# Fri3D_2024_ESP32.net
KiCad netlist of a schematic drawn in Altium Designer
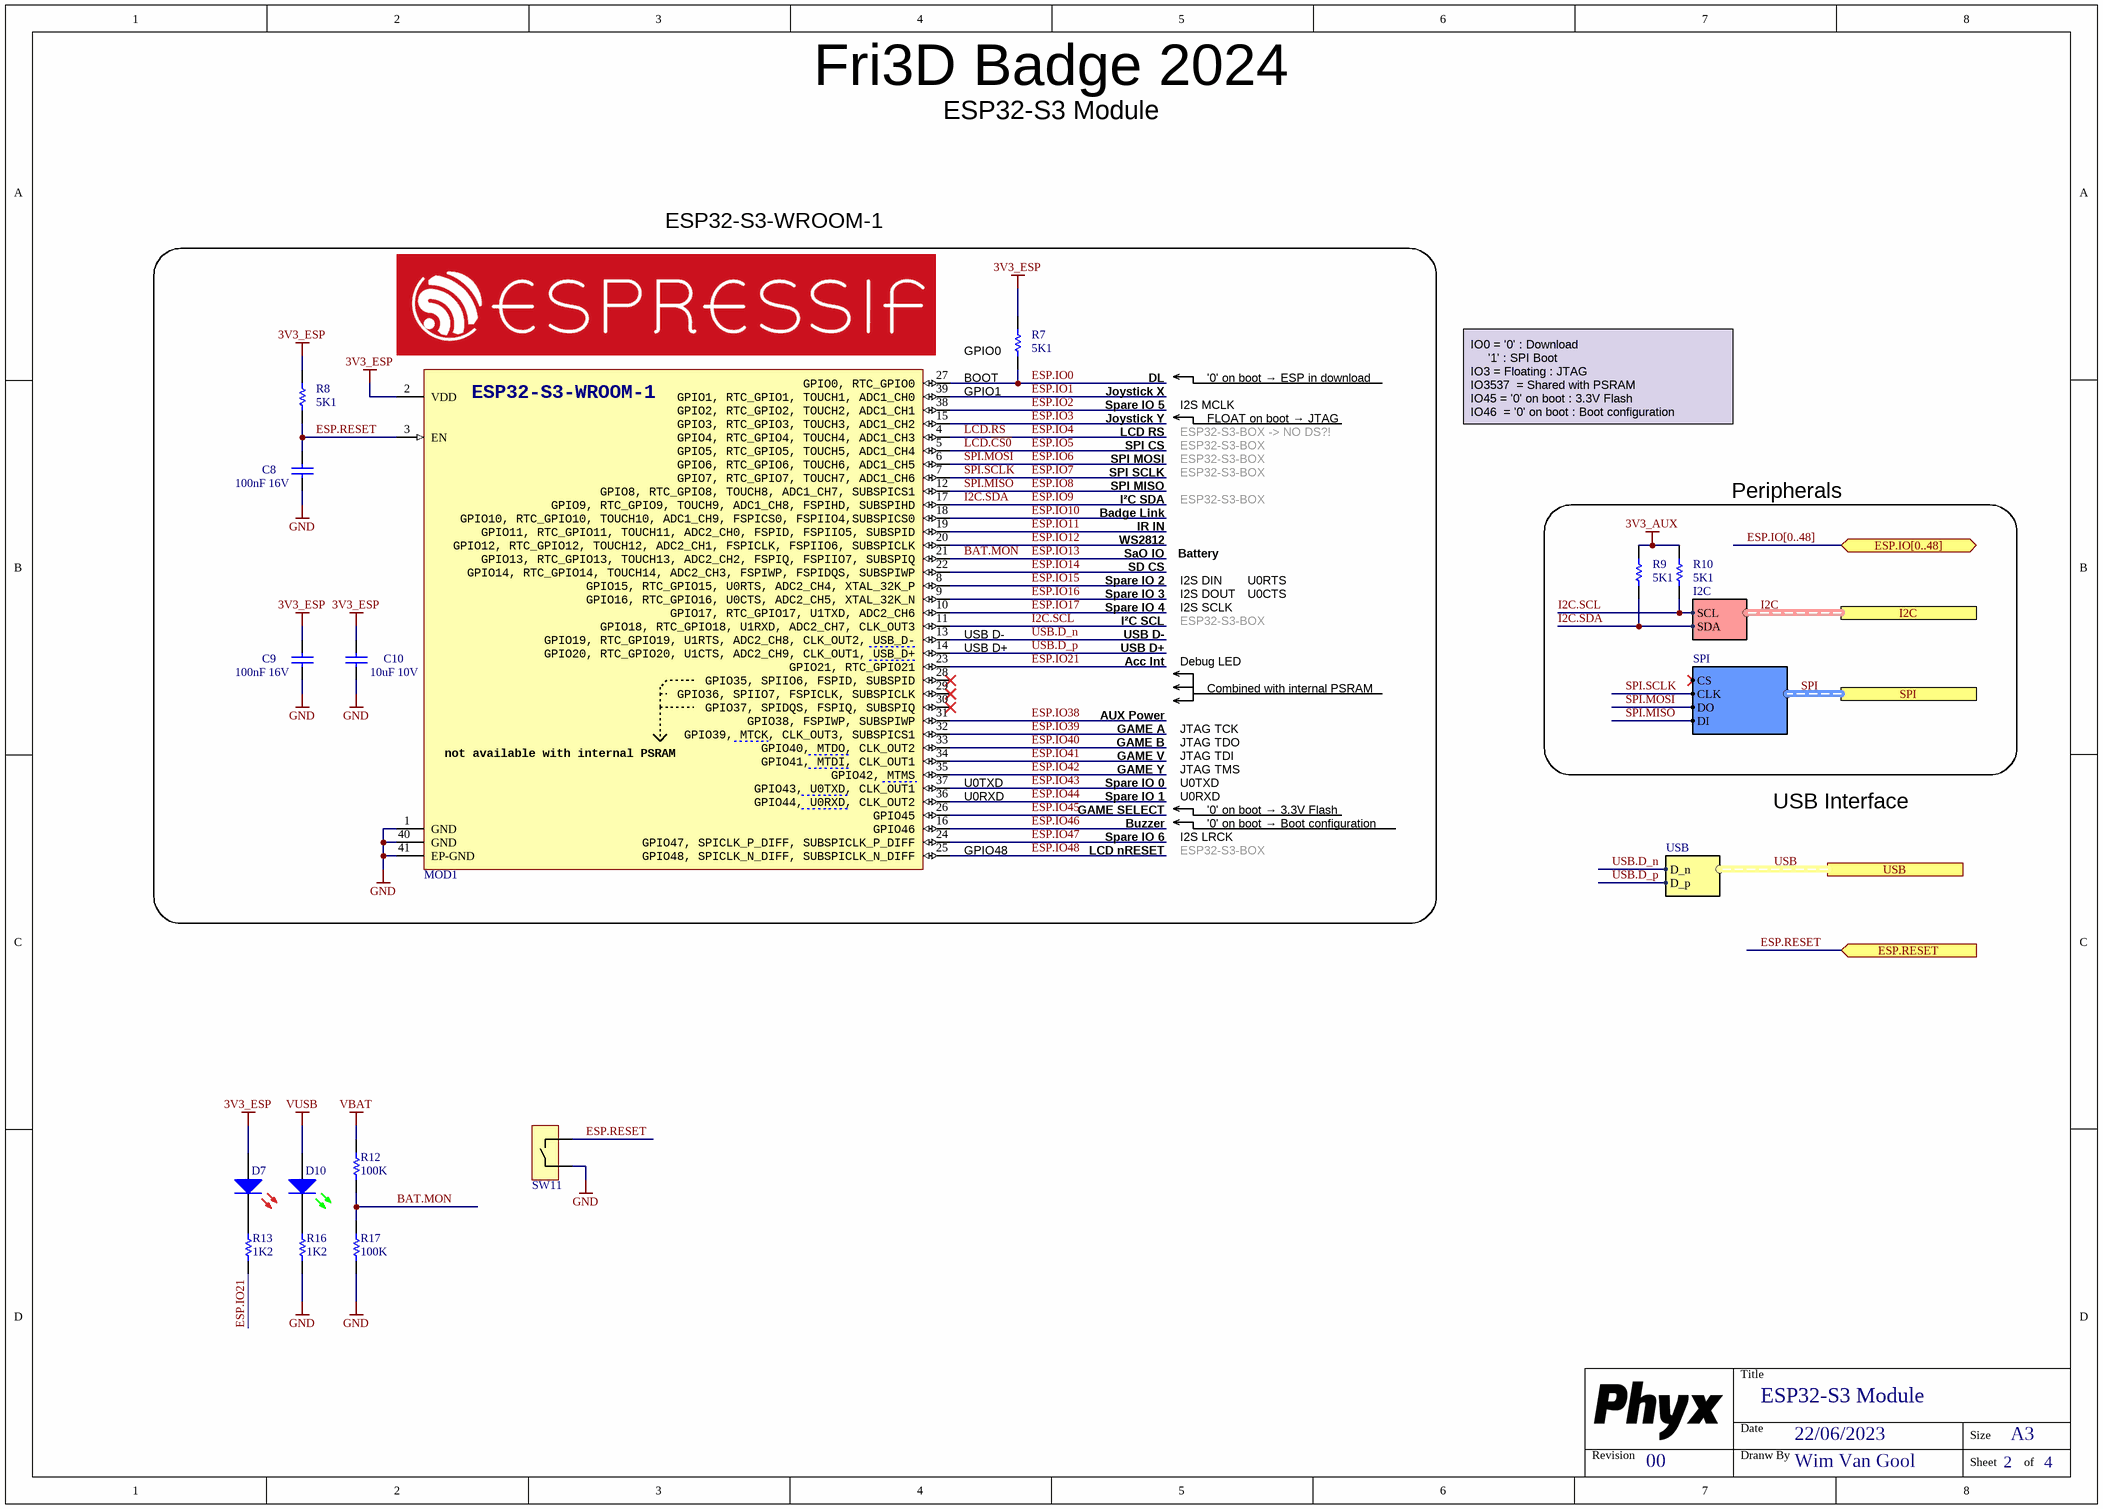
[diagram p0: Fri3D_2024_ESP32.SchDoc]

(export (version "E")
  (design (tool "Eeschema 10.0.6"))
  (components
    (comp (ref "C8")
      (value "100nF 16V")
      (footprint "C0603_N")
      (description "Capacitor Ceramic")
      (libsource (lib "Phyx_Components") (part "CAP_CERAMIC"))
    )
    (comp (ref "C9")
      (value "100nF 16V")
      (footprint "C0603_N")
      (description "Capacitor Ceramic")
      (libsource (lib "Phyx_Components") (part "CAP_CERAMIC"))
    )
    (comp (ref "C10")
      (value "10uF 10V")
      (footprint "C0805_N")
      (description "Capacitor Ceramic")
      (fields (field (name "Comment") "CAP_CERAMIC"))
      (libsource (lib "Phyx_Components") (part "CAP_CERAMIC"))
    )
    (comp (ref "D7")
      (value "Default 0805 Red LED")
      (footprint "LED_0805_RD")
      (description "=Description")
      (libsource (lib "Phyx_Components") (part "LED_RED"))
    )
    (comp (ref "D10")
      (value "Default 0805 Green LED")
      (footprint "LED_0805_GR")
      (description "=Description")
      (libsource (lib "Phyx_Components") (part "LED_GREEN"))
    )
    (comp (ref "MOD1")
      (value "ESP32-S3 based WROOM-1 16MB Flash, 8MB PSRAM")
      (footprint "ESP-ESP32-S3-WROOM-1")
      (description "WiFi # MOD ESP32-S3-WROOM-1")
      (libsource (lib "Phyx_Components") (part "ESP-ESP32-S3-WROOM-1"))
    )
    (comp (ref "R7")
      (value "5K1")
      (footprint "R0603_N")
      (fields (field (name "Comment") "RESISTOR"))
      (libsource (lib "Phyx_Components") (part "RESISTOR"))
    )
    (comp (ref "R8")
      (value "5K1")
      (footprint "R0603_N")
      (fields (field (name "Comment") "RESISTOR"))
      (libsource (lib "Phyx_Components") (part "RESISTOR"))
    )
    (comp (ref "R9")
      (value "5K1")
      (footprint "R0603_N")
      (fields (field (name "Comment") "RESISTOR"))
      (libsource (lib "Phyx_Components") (part "RESISTOR"))
    )
    (comp (ref "R10")
      (value "5K1")
      (footprint "R0603_N")
      (fields (field (name "Comment") "RESISTOR"))
      (libsource (lib "Phyx_Components") (part "RESISTOR"))
    )
    (comp (ref "R12")
      (value "100K")
      (footprint "R0603_N")
      (fields (field (name "Comment") "RESISTOR"))
      (libsource (lib "Phyx_Components") (part "RESISTOR"))
    )
    (comp (ref "R13")
      (value "1K2")
      (footprint "R0603_N")
      (fields (field (name "Comment") "RESISTOR"))
      (libsource (lib "Phyx_Components") (part "RESISTOR"))
    )
    (comp (ref "R16")
      (value "1K2")
      (footprint "R0603_N")
      (fields (field (name "Comment") "RESISTOR"))
      (libsource (lib "Phyx_Components") (part "RESISTOR"))
    )
    (comp (ref "R17")
      (value "100K")
      (footprint "R0603_N")
      (fields (field (name "Comment") "RESISTOR"))
      (libsource (lib "Phyx_Components") (part "RESISTOR"))
    )
    (comp (ref "SW11")
      (value "SKPMAME010 6x6 TACTG Switch")
      (footprint "ALPS_SKPMAME010")
      (libsource (lib "Phyx_Components") (part "SW_TACT"))
    )
  )
  (nets
    (net (code "23") (name "/ESP.IO0") (class "Default")
      (node (ref "MOD1") (pin "27") (pinfunction "GPIO0,_RTC_GPIO0_27") (pintype "bidirectional"))
      (node (ref "R7") (pin "2") (pinfunction "2_2") (pintype "passive"))
    )
    (net (code "24") (name "/ESP.IO1") (class "Default")
      (node (ref "MOD1") (pin "39") (pinfunction "GPIO1,_RTC_GPIO1,_TOUCH1,_ADC1_CH0_39") (pintype "bidirectional"))
    )
    (net (code "25") (name "/ESP.IO2") (class "Default")
      (node (ref "MOD1") (pin "38") (pinfunction "GPIO2,_RTC_GPIO2,_TOUCH2,_ADC1_CH1_38") (pintype "bidirectional"))
    )
    (net (code "26") (name "/ESP.IO3") (class "Default")
      (node (ref "MOD1") (pin "15") (pinfunction "GPIO3,_RTC_GPIO3,_TOUCH3,_ADC1_CH2_15") (pintype "bidirectional"))
    )
    (net (code "27") (name "/ESP.IO4") (class "Default")
      (node (ref "MOD1") (pin "4") (pinfunction "GPIO4,_RTC_GPIO4,_TOUCH4,_ADC1_CH3_4") (pintype "bidirectional"))
    )
    (net (code "28") (name "/ESP.IO5") (class "Default")
      (node (ref "MOD1") (pin "5") (pinfunction "GPIO5,_RTC_GPIO5,_TOUCH5,_ADC1_CH4_5") (pintype "bidirectional"))
    )
    (net (code "29") (name "/ESP.IO6") (class "Default")
      (node (ref "MOD1") (pin "6") (pinfunction "GPIO6,_RTC_GPIO6,_TOUCH6,_ADC1_CH5_6") (pintype "bidirectional"))
    )
    (net (code "30") (name "/ESP.IO7") (class "Default")
      (node (ref "MOD1") (pin "7") (pinfunction "GPIO7,_RTC_GPIO7,_TOUCH7,_ADC1_CH6_7") (pintype "bidirectional"))
    )
    (net (code "31") (name "/ESP.IO8") (class "Default")
      (node (ref "MOD1") (pin "12") (pinfunction "GPIO8,_RTC_GPIO8,_TOUCH8,_ADC1_CH7,_SUBSPICS1_12") (pintype "bidirectional"))
    )
    (net (code "32") (name "/ESP.IO9") (class "Default")
      (node (ref "MOD1") (pin "17") (pinfunction "GPIO9,_RTC_GPIO9,_TOUCH9,_ADC1_CH8,_FSPIHD,_SUBSPIHD_17") (pintype "bidirectional"))
      (node (ref "R9") (pin "2") (pinfunction "2_2") (pintype "passive"))
    )
    (net (code "33") (name "/ESP.IO10") (class "Default")
      (node (ref "MOD1") (pin "18") (pinfunction "GPIO10,_RTC_GPIO10,_TOUCH10,_ADC1_CH9,_FSPICS0,_FSPIIO4,SUBSPICS0_18") (pintype "bidirectional"))
    )
    (net (code "34") (name "/ESP.IO11") (class "Default")
      (node (ref "MOD1") (pin "19") (pinfunction "GPIO11,_RTC_GPIO11,_TOUCH11,_ADC2_CH0,_FSPID,_FSPIIO5,_SUBSPID_19") (pintype "bidirectional"))
    )
    (net (code "35") (name "/ESP.IO12") (class "Default")
      (node (ref "MOD1") (pin "20") (pinfunction "GPIO12,_RTC_GPIO12,_TOUCH12,_ADC2_CH1,_FSPICLK,_FSPIIO6,_SUBSPICLK_20") (pintype "bidirectional"))
    )
    (net (code "36") (name "/ESP.IO13") (class "Default")
      (node (ref "MOD1") (pin "21") (pinfunction "GPIO13,_RTC_GPIO13,_TOUCH13,_ADC2_CH2,_FSPIQ,_FSPIIO7,_SUBSPIQ_21") (pintype "bidirectional"))
      (node (ref "R12") (pin "2") (pinfunction "2_2") (pintype "passive"))
      (node (ref "R17") (pin "1") (pinfunction "1_1") (pintype "passive"))
    )
    (net (code "37") (name "/ESP.IO14") (class "Default")
      (node (ref "MOD1") (pin "22") (pinfunction "GPIO14,_RTC_GPIO14,_TOUCH14,_ADC2_CH3,_FSPIWP,_FSPIDQS,_SUBSPIWP_22") (pintype "bidirectional"))
    )
    (net (code "38") (name "/ESP.IO15") (class "Default")
      (node (ref "MOD1") (pin "8") (pinfunction "GPIO15,_RTC_GPIO15,_U0RTS,_ADC2_CH4,_XTAL_32K_P_8") (pintype "bidirectional"))
    )
    (net (code "39") (name "/ESP.IO16") (class "Default")
      (node (ref "MOD1") (pin "9") (pinfunction "GPIO16,_RTC_GPIO16,_U0CTS,_ADC2_CH5,_XTAL_32K_N_9") (pintype "bidirectional"))
    )
    (net (code "40") (name "/ESP.IO17") (class "Default")
      (node (ref "MOD1") (pin "10") (pinfunction "GPIO17,_RTC_GPIO17,_U1TXD,_ADC2_CH6_10") (pintype "bidirectional"))
    )
    (net (code "41") (name "/ESP.IO21") (class "Default")
      (node (ref "MOD1") (pin "23") (pinfunction "GPIO21,_RTC_GPIO21_23") (pintype "bidirectional"))
      (node (ref "R13") (pin "2") (pinfunction "2_2") (pintype "passive"))
    )
    (net (code "42") (name "/ESP.IO38") (class "Default")
      (node (ref "MOD1") (pin "31") (pinfunction "GPIO38,_FSPIWP,_SUBSPIWP_31") (pintype "bidirectional"))
    )
    (net (code "43") (name "/ESP.IO39") (class "Default")
      (node (ref "MOD1") (pin "32") (pinfunction "GPIO39,_MTCK,_CLK_OUT3,_SUBSPICS1_32") (pintype "bidirectional"))
    )
    (net (code "44") (name "/ESP.IO40") (class "Default")
      (node (ref "MOD1") (pin "33") (pinfunction "GPIO40,_MTDO,_CLK_OUT2_33") (pintype "bidirectional"))
    )
    (net (code "45") (name "/ESP.IO41") (class "Default")
      (node (ref "MOD1") (pin "34") (pinfunction "GPIO41,_MTDI,_CLK_OUT1_34") (pintype "bidirectional"))
    )
    (net (code "46") (name "/ESP.IO42") (class "Default")
      (node (ref "MOD1") (pin "35") (pinfunction "GPIO42,_MTMS_35") (pintype "bidirectional"))
    )
    (net (code "47") (name "/ESP.IO43") (class "Default")
      (node (ref "MOD1") (pin "37") (pinfunction "GPIO43,_U0TXD,_CLK_OUT1_37") (pintype "bidirectional"))
    )
    (net (code "48") (name "/ESP.IO44") (class "Default")
      (node (ref "MOD1") (pin "36") (pinfunction "GPIO44,_U0RXD,_CLK_OUT2_36") (pintype "bidirectional"))
    )
    (net (code "49") (name "/ESP.IO45") (class "Default")
      (node (ref "MOD1") (pin "26") (pinfunction "GPIO45_26") (pintype "bidirectional"))
    )
    (net (code "50") (name "/ESP.IO46") (class "Default")
      (node (ref "MOD1") (pin "16") (pinfunction "GPIO46_16") (pintype "bidirectional"))
    )
    (net (code "51") (name "/ESP.IO47") (class "Default")
      (node (ref "MOD1") (pin "24") (pinfunction "GPIO47,_SPICLK_P_DIFF,_SUBSPICLK_P_DIFF_24") (pintype "bidirectional"))
    )
    (net (code "52") (name "/ESP.IO48") (class "Default")
      (node (ref "MOD1") (pin "25") (pinfunction "GPIO48,_SPICLK_N_DIFF,_SUBSPICLK_N_DIFF_25") (pintype "bidirectional"))
    )
    (net (code "54") (name "/ESP.RESET") (class "Default")
      (node (ref "C8") (pin "1") (pinfunction "1_1") (pintype "passive"))
      (node (ref "MOD1") (pin "3") (pinfunction "EN_3") (pintype "input"))
      (node (ref "R8") (pin "2") (pinfunction "2_2") (pintype "passive"))
      (node (ref "SW11") (pin "1") (pinfunction "1_1") (pintype "passive"))
    )
    (net (code "55") (name "/I2C.SCL") (class "Default")
      (node (ref "MOD1") (pin "11") (pinfunction "GPIO18,_RTC_GPIO18,_U1RXD,_ADC2_CH7,_CLK_OUT3_11") (pintype "bidirectional"))
      (node (ref "R10") (pin "2") (pinfunction "2_2") (pintype "passive"))
    )
    (net (code "58") (name "/USB.D_n") (class "Default")
      (node (ref "MOD1") (pin "13") (pinfunction "GPIO19,_RTC_GPIO19,_U1RTS,_ADC2_CH8,_CLK_OUT2,_USB_D-_13") (pintype "bidirectional"))
    )
    (net (code "59") (name "/USB.D_p") (class "Default")
      (node (ref "MOD1") (pin "14") (pinfunction "GPIO20,_RTC_GPIO20,_U1CTS,_ADC2_CH9,_CLK_OUT1,_USB_D+_14") (pintype "bidirectional"))
    )
    (net (code "61") (name "3V3_AUX") (class "Default")
      (node (ref "R10") (pin "1") (pinfunction "1_1") (pintype "passive"))
      (node (ref "R9") (pin "1") (pinfunction "1_1") (pintype "passive"))
    )
    (net (code "62") (name "3V3_ESP") (class "Default")
      (node (ref "C10") (pin "1") (pinfunction "1_1") (pintype "passive"))
      (node (ref "C9") (pin "1") (pinfunction "1_1") (pintype "passive"))
      (node (ref "D7") (pin "1") (pinfunction "A_1") (pintype "passive"))
      (node (ref "MOD1") (pin "2") (pinfunction "VDD_2") (pintype "power_in"))
      (node (ref "R7") (pin "1") (pinfunction "1_1") (pintype "passive"))
      (node (ref "R8") (pin "1") (pinfunction "1_1") (pintype "passive"))
    )
    (net (code "63") (name "GND") (class "Default")
      (node (ref "C10") (pin "2") (pinfunction "2_2") (pintype "passive"))
      (node (ref "C8") (pin "2") (pinfunction "2_2") (pintype "passive"))
      (node (ref "C9") (pin "2") (pinfunction "2_2") (pintype "passive"))
      (node (ref "MOD1") (pin "1") (pinfunction "GND_1") (pintype "power_in"))
      (node (ref "MOD1") (pin "40") (pinfunction "GND_40") (pintype "power_in"))
      (node (ref "MOD1") (pin "41") (pinfunction "EP-GND_41") (pintype "power_in"))
      (node (ref "R16") (pin "2") (pinfunction "2_2") (pintype "passive"))
      (node (ref "R17") (pin "2") (pinfunction "2_2") (pintype "passive"))
      (node (ref "SW11") (pin "2") (pinfunction "2_2") (pintype "passive"))
    )
    (net (code "64") (name "Net-(D7-K)") (class "Default")
      (node (ref "D7") (pin "2") (pinfunction "K_2") (pintype "passive"))
      (node (ref "R13") (pin "1") (pinfunction "1_1") (pintype "passive"))
    )
    (net (code "65") (name "Net-(D10-K)") (class "Default")
      (node (ref "D10") (pin "2") (pinfunction "K_2") (pintype "passive"))
      (node (ref "R16") (pin "1") (pinfunction "1_1") (pintype "passive"))
    )
    (net (code "66") (name "VBAT") (class "Default")
      (node (ref "R12") (pin "1") (pinfunction "1_1") (pintype "passive"))
    )
    (net (code "67") (name "VUSB") (class "Default")
      (node (ref "D10") (pin "1") (pinfunction "A_1") (pintype "passive"))
    )
    (net (code "68") (name "unconnected-(MOD1-GPIO35,_SPIIO6,_FSPID,_SUBSPID-Pad28)") (class "Default")
      (node (ref "MOD1") (pin "28") (pinfunction "GPIO35,_SPIIO6,_FSPID,_SUBSPID_28") (pintype "bidirectional+no_connect"))
    )
    (net (code "69") (name "unconnected-(MOD1-GPIO36,_SPIIO7,_FSPICLK,_SUBSPICLK-Pad29)") (class "Default")
      (node (ref "MOD1") (pin "29") (pinfunction "GPIO36,_SPIIO7,_FSPICLK,_SUBSPICLK_29") (pintype "bidirectional+no_connect"))
    )
    (net (code "70") (name "unconnected-(MOD1-GPIO37,_SPIDQS,_FSPIQ,_SUBSPIQ-Pad30)") (class "Default")
      (node (ref "MOD1") (pin "30") (pinfunction "GPIO37,_SPIDQS,_FSPIQ,_SUBSPIQ_30") (pintype "bidirectional+no_connect"))
    )
  )
)
